# PLCPart.net
KiCad netlist of a schematic drawn in EAGLE
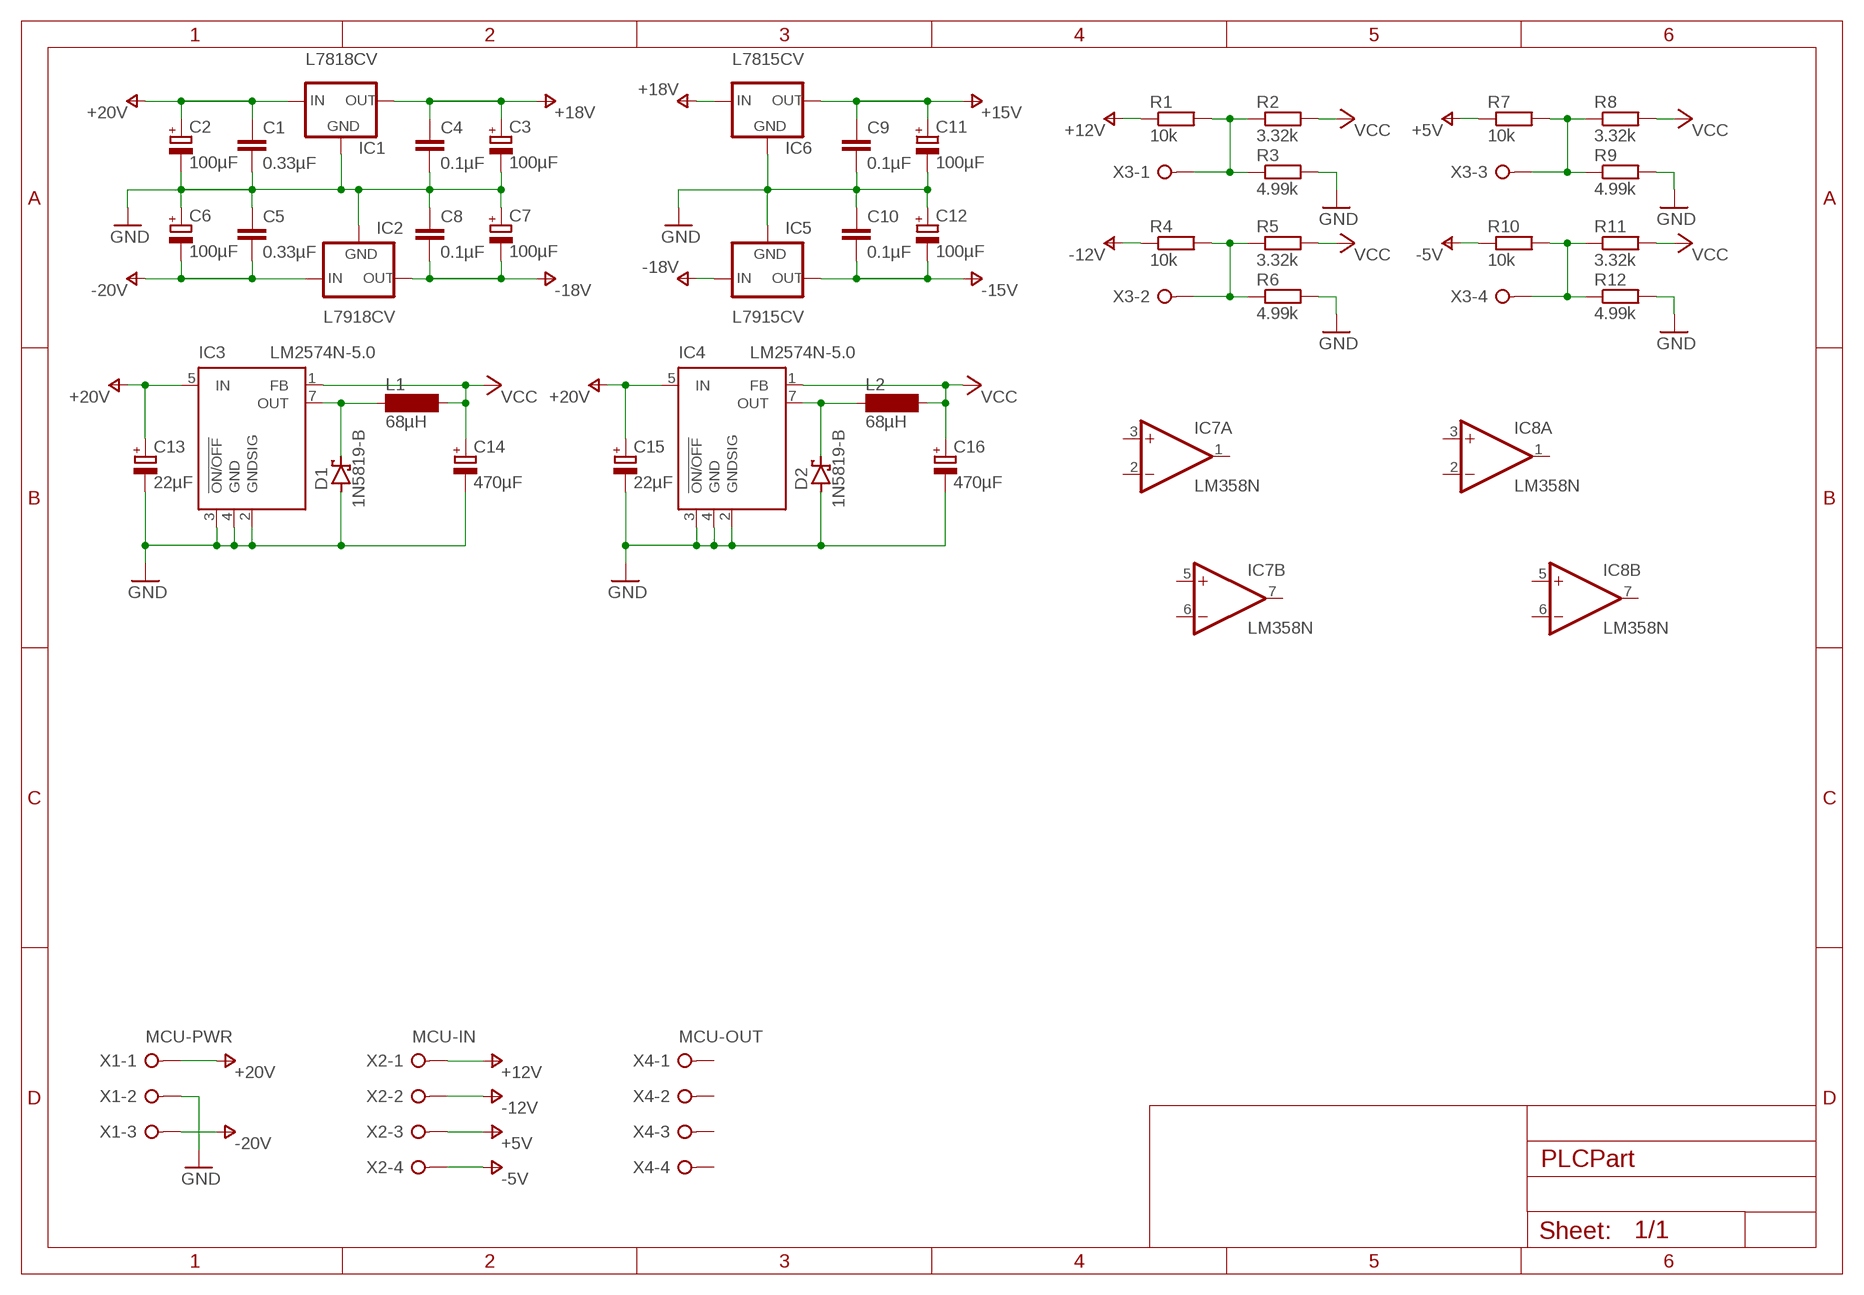
[diagram p0: schematic, sheet 1]

(export (version "E")
  (design (tool "Eeschema 10.0.6"))
  (components
    (comp (ref "C1")
      (value "0.33µF")
      (footprint "eagle-import:C050-024X044")
      (libsource (lib "eagle-import") (part "C-EU050-024X044"))
    )
    (comp (ref "C2")
      (value "100µF")
      (footprint "eagle-import:E2,5-6")
      (libsource (lib "eagle-import") (part "CPOL-EUE2.5-6"))
    )
    (comp (ref "C3")
      (value "100µF")
      (footprint "eagle-import:E2,5-6")
      (libsource (lib "eagle-import") (part "CPOL-EUE2.5-6"))
    )
    (comp (ref "C4")
      (value "0.1µF")
      (footprint "eagle-import:C050-024X044")
      (libsource (lib "eagle-import") (part "C-EU050-024X044"))
    )
    (comp (ref "C5")
      (value "0.33µF")
      (footprint "eagle-import:C050-024X044")
      (libsource (lib "eagle-import") (part "C-EU050-024X044"))
    )
    (comp (ref "C6")
      (value "100µF")
      (footprint "eagle-import:E2,5-6")
      (libsource (lib "eagle-import") (part "CPOL-EUE2.5-6"))
    )
    (comp (ref "C7")
      (value "100µF")
      (footprint "eagle-import:E2,5-6")
      (libsource (lib "eagle-import") (part "CPOL-EUE2.5-6"))
    )
    (comp (ref "C8")
      (value "0.1µF")
      (footprint "eagle-import:C050-024X044")
      (libsource (lib "eagle-import") (part "C-EU050-024X044"))
    )
    (comp (ref "C9")
      (value "0.1µF")
      (footprint "eagle-import:C050-024X044")
      (libsource (lib "eagle-import") (part "C-EU050-024X044"))
    )
    (comp (ref "C10")
      (value "0.1µF")
      (footprint "eagle-import:C050-024X044")
      (libsource (lib "eagle-import") (part "C-EU050-024X044"))
    )
    (comp (ref "C11")
      (value "100µF")
      (footprint "eagle-import:E2,5-6")
      (libsource (lib "eagle-import") (part "CPOL-EUE2.5-6"))
    )
    (comp (ref "C12")
      (value "100µF")
      (footprint "eagle-import:E2,5-6")
      (libsource (lib "eagle-import") (part "CPOL-EUE2.5-6"))
    )
    (comp (ref "C13")
      (value "22µF")
      (footprint "eagle-import:E2-5")
      (libsource (lib "eagle-import") (part "CPOL-EUE2-5"))
    )
    (comp (ref "C14")
      (value "470µF")
      (footprint "eagle-import:E2-5")
      (libsource (lib "eagle-import") (part "CPOL-EUE2-5"))
    )
    (comp (ref "C15")
      (value "22µF")
      (footprint "eagle-import:E2-5")
      (libsource (lib "eagle-import") (part "CPOL-EUE2-5"))
    )
    (comp (ref "C16")
      (value "470µF")
      (footprint "eagle-import:E2-5")
      (libsource (lib "eagle-import") (part "CPOL-EUE2-5"))
    )
    (comp (ref "D1")
      (value "1N5819-B")
      (footprint "eagle-import:DO41-7.6")
      (libsource (lib "eagle-import") (part "1N5819-B"))
    )
    (comp (ref "D2")
      (value "1N5819-B")
      (footprint "eagle-import:DO41-7.6")
      (libsource (lib "eagle-import") (part "1N5819-B"))
    )
    (comp (ref "IC1")
      (value "L7818CV")
      (footprint "eagle-import:78XXS")
      (libsource (lib "eagle-import") (part "78XXS"))
    )
    (comp (ref "IC2")
      (value "L7918CV")
      (footprint "eagle-import:79XXS")
      (libsource (lib "eagle-import") (part "79XXS"))
    )
    (comp (ref "IC3")
      (value "LM2574N-5.0")
      (footprint "eagle-import:DIL08")
      (libsource (lib "eagle-import") (part "LM2574?-N5.0"))
    )
    (comp (ref "IC4")
      (value "LM2574N-5.0")
      (footprint "eagle-import:DIL08")
      (libsource (lib "eagle-import") (part "LM2574?-N5.0"))
    )
    (comp (ref "IC5")
      (value "L7915CV")
      (footprint "eagle-import:79XXS")
      (libsource (lib "eagle-import") (part "79XXS"))
    )
    (comp (ref "IC6")
      (value "L7815CV")
      (footprint "eagle-import:78XXS")
      (libsource (lib "eagle-import") (part "78XXS"))
    )
    (comp (ref "IC7")
      (value "LM358N")
      (footprint "eagle-import:DIL08")
      (libsource (lib "eagle-import") (part "LM358N"))
    )
    (comp (ref "IC8")
      (value "LM358N")
      (footprint "eagle-import:DIL08")
      (libsource (lib "eagle-import") (part "LM358N"))
    )
    (comp (ref "L1")
      (value "68µH")
      (footprint "eagle-import:SD12K100")
      (libsource (lib "eagle-import") (part "SD12K100"))
    )
    (comp (ref "L2")
      (value "68µH")
      (footprint "eagle-import:SD12K100")
      (libsource (lib "eagle-import") (part "SD12K100"))
    )
    (comp (ref "R1")
      (value "10k")
      (footprint "eagle-import:0207_10")
      (libsource (lib "eagle-import") (part "R-EU_0207/10"))
    )
    (comp (ref "R2")
      (value "3.32k")
      (footprint "eagle-import:0207_10")
      (libsource (lib "eagle-import") (part "R-EU_0207/10"))
    )
    (comp (ref "R3")
      (value "4.99k")
      (footprint "eagle-import:0207_10")
      (libsource (lib "eagle-import") (part "R-EU_0207/10"))
    )
    (comp (ref "R4")
      (value "10k")
      (footprint "eagle-import:0207_10")
      (libsource (lib "eagle-import") (part "R-EU_0207/10"))
    )
    (comp (ref "R5")
      (value "3.32k")
      (footprint "eagle-import:0207_10")
      (libsource (lib "eagle-import") (part "R-EU_0207/10"))
    )
    (comp (ref "R6")
      (value "4.99k")
      (footprint "eagle-import:0207_10")
      (libsource (lib "eagle-import") (part "R-EU_0207/10"))
    )
    (comp (ref "R7")
      (value "10k")
      (footprint "eagle-import:0207_10")
      (libsource (lib "eagle-import") (part "R-EU_0207/10"))
    )
    (comp (ref "R8")
      (value "3.32k")
      (footprint "eagle-import:0207_10")
      (libsource (lib "eagle-import") (part "R-EU_0207/10"))
    )
    (comp (ref "R9")
      (value "4.99k")
      (footprint "eagle-import:0207_10")
      (libsource (lib "eagle-import") (part "R-EU_0207/10"))
    )
    (comp (ref "R10")
      (value "10k")
      (footprint "eagle-import:0207_10")
      (libsource (lib "eagle-import") (part "R-EU_0207/10"))
    )
    (comp (ref "R11")
      (value "3.32k")
      (footprint "eagle-import:0207_10")
      (libsource (lib "eagle-import") (part "R-EU_0207/10"))
    )
    (comp (ref "R12")
      (value "4.99k")
      (footprint "eagle-import:0207_10")
      (libsource (lib "eagle-import") (part "R-EU_0207/10"))
    )
    (comp (ref "X1")
      (value "MCU-PWR")
      (footprint "eagle-import:W237-133")
      (libsource (lib "eagle-import") (part "W237-03P"))
    )
    (comp (ref "X2")
      (value "MCU-IN")
      (footprint "eagle-import:W237-4P")
      (libsource (lib "eagle-import") (part "W237-04P"))
    )
    (comp (ref "X3")
      (value "W237-04P")
      (footprint "eagle-import:W237-4P")
      (libsource (lib "eagle-import") (part "W237-04P"))
    )
    (comp (ref "X4")
      (value "MCU-OUT")
      (footprint "eagle-import:W237-4P")
      (libsource (lib "eagle-import") (part "W237-04P"))
    )
  )
  (nets
    (net (code "1") (name "+5V") (class "Default")
      (node (ref "R7") (pin "1") (pinfunction "1_1") (pintype "passive"))
      (node (ref "X2") (pin "3") (pinfunction "KL_3") (pintype "passive"))
    )
    (net (code "2") (name "+12V") (class "Default")
      (node (ref "R1") (pin "1") (pinfunction "1_1") (pintype "passive"))
      (node (ref "X2") (pin "1") (pinfunction "KL_1") (pintype "passive"))
    )
    (net (code "3") (name "+15V") (class "Default")
      (node (ref "C11") (pin "+") (pinfunction "+_+") (pintype "passive"))
      (node (ref "C9") (pin "1") (pinfunction "1_1") (pintype "passive"))
      (node (ref "IC6") (pin "OUT") (pinfunction "OUT_OUT") (pintype "passive"))
    )
    (net (code "4") (name "+18V") (class "Default")
      (node (ref "C3") (pin "+") (pinfunction "+_+") (pintype "passive"))
      (node (ref "C4") (pin "1") (pinfunction "1_1") (pintype "passive"))
      (node (ref "IC1") (pin "OUT") (pinfunction "OUT_OUT") (pintype "passive"))
      (node (ref "IC6") (pin "IN") (pinfunction "IN_IN") (pintype "input"))
    )
    (net (code "5") (name "+20V") (class "Default")
      (node (ref "C1") (pin "1") (pinfunction "1_1") (pintype "passive"))
      (node (ref "C13") (pin "+") (pinfunction "+_+") (pintype "passive"))
      (node (ref "C15") (pin "+") (pinfunction "+_+") (pintype "passive"))
      (node (ref "C2") (pin "+") (pinfunction "+_+") (pintype "passive"))
      (node (ref "IC1") (pin "IN") (pinfunction "IN_IN") (pintype "input"))
      (node (ref "IC3") (pin "5") (pinfunction "IN_5") (pintype "input"))
      (node (ref "IC4") (pin "5") (pinfunction "IN_5") (pintype "input"))
      (node (ref "X1") (pin "1") (pinfunction "KL_1") (pintype "passive"))
    )
    (net (code "6") (name "-5V") (class "Default")
      (node (ref "R10") (pin "1") (pinfunction "1_1") (pintype "passive"))
      (node (ref "X2") (pin "4") (pinfunction "KL_4") (pintype "passive"))
    )
    (net (code "7") (name "-12V") (class "Default")
      (node (ref "R4") (pin "1") (pinfunction "1_1") (pintype "passive"))
      (node (ref "X2") (pin "2") (pinfunction "KL_2") (pintype "passive"))
    )
    (net (code "8") (name "-15V") (class "Default")
      (node (ref "C10") (pin "2") (pinfunction "2_2") (pintype "passive"))
      (node (ref "C12") (pin "-") (pinfunction "-_-") (pintype "passive"))
      (node (ref "IC5") (pin "OUT") (pinfunction "OUT_OUT") (pintype "passive"))
    )
    (net (code "9") (name "-18V") (class "Default")
      (node (ref "C7") (pin "-") (pinfunction "-_-") (pintype "passive"))
      (node (ref "C8") (pin "2") (pinfunction "2_2") (pintype "passive"))
      (node (ref "IC2") (pin "OUT") (pinfunction "OUT_OUT") (pintype "passive"))
      (node (ref "IC5") (pin "IN") (pinfunction "IN_IN") (pintype "input"))
    )
    (net (code "10") (name "-20V") (class "Default")
      (node (ref "C5") (pin "2") (pinfunction "2_2") (pintype "passive"))
      (node (ref "C6") (pin "-") (pinfunction "-_-") (pintype "passive"))
      (node (ref "IC2") (pin "IN") (pinfunction "IN_IN") (pintype "input"))
      (node (ref "X1") (pin "3") (pinfunction "KL_3") (pintype "passive"))
    )
    (net (code "11") (name "GND") (class "Default")
      (node (ref "C1") (pin "2") (pinfunction "2_2") (pintype "passive"))
      (node (ref "C10") (pin "1") (pinfunction "1_1") (pintype "passive"))
      (node (ref "C11") (pin "-") (pinfunction "-_-") (pintype "passive"))
      (node (ref "C12") (pin "+") (pinfunction "+_+") (pintype "passive"))
      (node (ref "C13") (pin "-") (pinfunction "-_-") (pintype "passive"))
      (node (ref "C14") (pin "-") (pinfunction "-_-") (pintype "passive"))
      (node (ref "C15") (pin "-") (pinfunction "-_-") (pintype "passive"))
      (node (ref "C16") (pin "-") (pinfunction "-_-") (pintype "passive"))
      (node (ref "C2") (pin "-") (pinfunction "-_-") (pintype "passive"))
      (node (ref "C3") (pin "-") (pinfunction "-_-") (pintype "passive"))
      (node (ref "C4") (pin "2") (pinfunction "2_2") (pintype "passive"))
      (node (ref "C5") (pin "1") (pinfunction "1_1") (pintype "passive"))
      (node (ref "C6") (pin "+") (pinfunction "+_+") (pintype "passive"))
      (node (ref "C7") (pin "+") (pinfunction "+_+") (pintype "passive"))
      (node (ref "C8") (pin "1") (pinfunction "1_1") (pintype "passive"))
      (node (ref "C9") (pin "2") (pinfunction "2_2") (pintype "passive"))
      (node (ref "D1") (pin "A") (pinfunction "A_A") (pintype "passive"))
      (node (ref "D2") (pin "A") (pinfunction "A_A") (pintype "passive"))
      (node (ref "IC1") (pin "GND") (pinfunction "GND_GND") (pintype "input"))
      (node (ref "IC2") (pin "GND") (pinfunction "GND_GND") (pintype "input"))
      (node (ref "IC3") (pin "2") (pinfunction "GNDSIG_2") (pintype "input"))
      (node (ref "IC3") (pin "3") (pinfunction "~{ON/OFF}_3") (pintype "input"))
      (node (ref "IC3") (pin "4") (pinfunction "GND_4") (pintype "power_in"))
      (node (ref "IC4") (pin "2") (pinfunction "GNDSIG_2") (pintype "input"))
      (node (ref "IC4") (pin "3") (pinfunction "~{ON/OFF}_3") (pintype "input"))
      (node (ref "IC4") (pin "4") (pinfunction "GND_4") (pintype "power_in"))
      (node (ref "IC5") (pin "GND") (pinfunction "GND_GND") (pintype "input"))
      (node (ref "IC6") (pin "GND") (pinfunction "GND_GND") (pintype "input"))
      (node (ref "R12") (pin "2") (pinfunction "2_2") (pintype "passive"))
      (node (ref "R3") (pin "2") (pinfunction "2_2") (pintype "passive"))
      (node (ref "R6") (pin "2") (pinfunction "2_2") (pintype "passive"))
      (node (ref "R9") (pin "2") (pinfunction "2_2") (pintype "passive"))
      (node (ref "X1") (pin "2") (pinfunction "KL_2") (pintype "passive"))
    )
    (net (code "12") (name "Net-(IC3-OUT)") (class "Default")
      (node (ref "D1") (pin "C") (pinfunction "C_C") (pintype "passive"))
      (node (ref "IC3") (pin "7") (pinfunction "OUT_7") (pintype "passive"))
      (node (ref "L1") (pin "1") (pinfunction "1_1") (pintype "passive"))
    )
    (net (code "13") (name "Net-(IC4-OUT)") (class "Default")
      (node (ref "D2") (pin "C") (pinfunction "C_C") (pintype "passive"))
      (node (ref "IC4") (pin "7") (pinfunction "OUT_7") (pintype "passive"))
      (node (ref "L2") (pin "1") (pinfunction "1_1") (pintype "passive"))
    )
    (net (code "14") (name "Net-(X3A-KL)") (class "Default")
      (node (ref "R1") (pin "2") (pinfunction "2_2") (pintype "passive"))
      (node (ref "R2") (pin "1") (pinfunction "1_1") (pintype "passive"))
      (node (ref "R3") (pin "1") (pinfunction "1_1") (pintype "passive"))
      (node (ref "X3") (pin "1") (pinfunction "KL_1") (pintype "passive"))
    )
    (net (code "15") (name "Net-(X3B-KL)") (class "Default")
      (node (ref "R4") (pin "2") (pinfunction "2_2") (pintype "passive"))
      (node (ref "R5") (pin "1") (pinfunction "1_1") (pintype "passive"))
      (node (ref "R6") (pin "1") (pinfunction "1_1") (pintype "passive"))
      (node (ref "X3") (pin "2") (pinfunction "KL_2") (pintype "passive"))
    )
    (net (code "16") (name "Net-(X3C-KL)") (class "Default")
      (node (ref "R7") (pin "2") (pinfunction "2_2") (pintype "passive"))
      (node (ref "R8") (pin "1") (pinfunction "1_1") (pintype "passive"))
      (node (ref "R9") (pin "1") (pinfunction "1_1") (pintype "passive"))
      (node (ref "X3") (pin "3") (pinfunction "KL_3") (pintype "passive"))
    )
    (net (code "17") (name "Net-(X3D-KL)") (class "Default")
      (node (ref "R10") (pin "2") (pinfunction "2_2") (pintype "passive"))
      (node (ref "R11") (pin "1") (pinfunction "1_1") (pintype "passive"))
      (node (ref "R12") (pin "1") (pinfunction "1_1") (pintype "passive"))
      (node (ref "X3") (pin "4") (pinfunction "KL_4") (pintype "passive"))
    )
    (net (code "18") (name "VCC") (class "Default")
      (node (ref "C14") (pin "+") (pinfunction "+_+") (pintype "passive"))
      (node (ref "C16") (pin "+") (pinfunction "+_+") (pintype "passive"))
      (node (ref "IC3") (pin "1") (pinfunction "FB_1") (pintype "input"))
      (node (ref "IC4") (pin "1") (pinfunction "FB_1") (pintype "input"))
      (node (ref "L1") (pin "2") (pinfunction "2_2") (pintype "passive"))
      (node (ref "L2") (pin "2") (pinfunction "2_2") (pintype "passive"))
      (node (ref "R11") (pin "2") (pinfunction "2_2") (pintype "passive"))
      (node (ref "R2") (pin "2") (pinfunction "2_2") (pintype "passive"))
      (node (ref "R5") (pin "2") (pinfunction "2_2") (pintype "passive"))
      (node (ref "R8") (pin "2") (pinfunction "2_2") (pintype "passive"))
    )
    (net (code "19") (name "unconnected-(IC7A-+IN-Pad3)") (class "Default")
      (node (ref "IC7") (pin "3") (pinfunction "+IN_3") (pintype "input"))
    )
    (net (code "20") (name "unconnected-(IC7A--IN-Pad2)") (class "Default")
      (node (ref "IC7") (pin "2") (pinfunction "-IN_2") (pintype "input"))
    )
    (net (code "21") (name "unconnected-(IC7A-OUT-Pad1)") (class "Default")
      (node (ref "IC7") (pin "1") (pinfunction "OUT_1") (pintype "output"))
    )
    (net (code "22") (name "unconnected-(IC7B-+IN-Pad5)") (class "Default")
      (node (ref "IC7") (pin "5") (pinfunction "+IN_5") (pintype "input"))
    )
    (net (code "23") (name "unconnected-(IC7B--IN-Pad6)") (class "Default")
      (node (ref "IC7") (pin "6") (pinfunction "-IN_6") (pintype "input"))
    )
    (net (code "24") (name "unconnected-(IC7B-OUT-Pad7)") (class "Default")
      (node (ref "IC7") (pin "7") (pinfunction "OUT_7") (pintype "output"))
    )
    (net (code "25") (name "unconnected-(IC8A-+IN-Pad3)") (class "Default")
      (node (ref "IC8") (pin "3") (pinfunction "+IN_3") (pintype "input"))
    )
    (net (code "26") (name "unconnected-(IC8A--IN-Pad2)") (class "Default")
      (node (ref "IC8") (pin "2") (pinfunction "-IN_2") (pintype "input"))
    )
    (net (code "27") (name "unconnected-(IC8A-OUT-Pad1)") (class "Default")
      (node (ref "IC8") (pin "1") (pinfunction "OUT_1") (pintype "output"))
    )
    (net (code "28") (name "unconnected-(IC8B-+IN-Pad5)") (class "Default")
      (node (ref "IC8") (pin "5") (pinfunction "+IN_5") (pintype "input"))
    )
    (net (code "29") (name "unconnected-(IC8B--IN-Pad6)") (class "Default")
      (node (ref "IC8") (pin "6") (pinfunction "-IN_6") (pintype "input"))
    )
    (net (code "30") (name "unconnected-(IC8B-OUT-Pad7)") (class "Default")
      (node (ref "IC8") (pin "7") (pinfunction "OUT_7") (pintype "output"))
    )
    (net (code "31") (name "unconnected-(X4A-KL-Pad1)") (class "Default")
      (node (ref "X4") (pin "1") (pinfunction "KL_1") (pintype "passive"))
    )
    (net (code "32") (name "unconnected-(X4B-KL-Pad2)") (class "Default")
      (node (ref "X4") (pin "2") (pinfunction "KL_2") (pintype "passive"))
    )
    (net (code "33") (name "unconnected-(X4C-KL-Pad3)") (class "Default")
      (node (ref "X4") (pin "3") (pinfunction "KL_3") (pintype "passive"))
    )
    (net (code "34") (name "unconnected-(X4D-KL-Pad4)") (class "Default")
      (node (ref "X4") (pin "4") (pinfunction "KL_4") (pintype "passive"))
    )
  )
)
